# boost-demux_v1.net
KiCad netlist of a schematic drawn in EAGLE
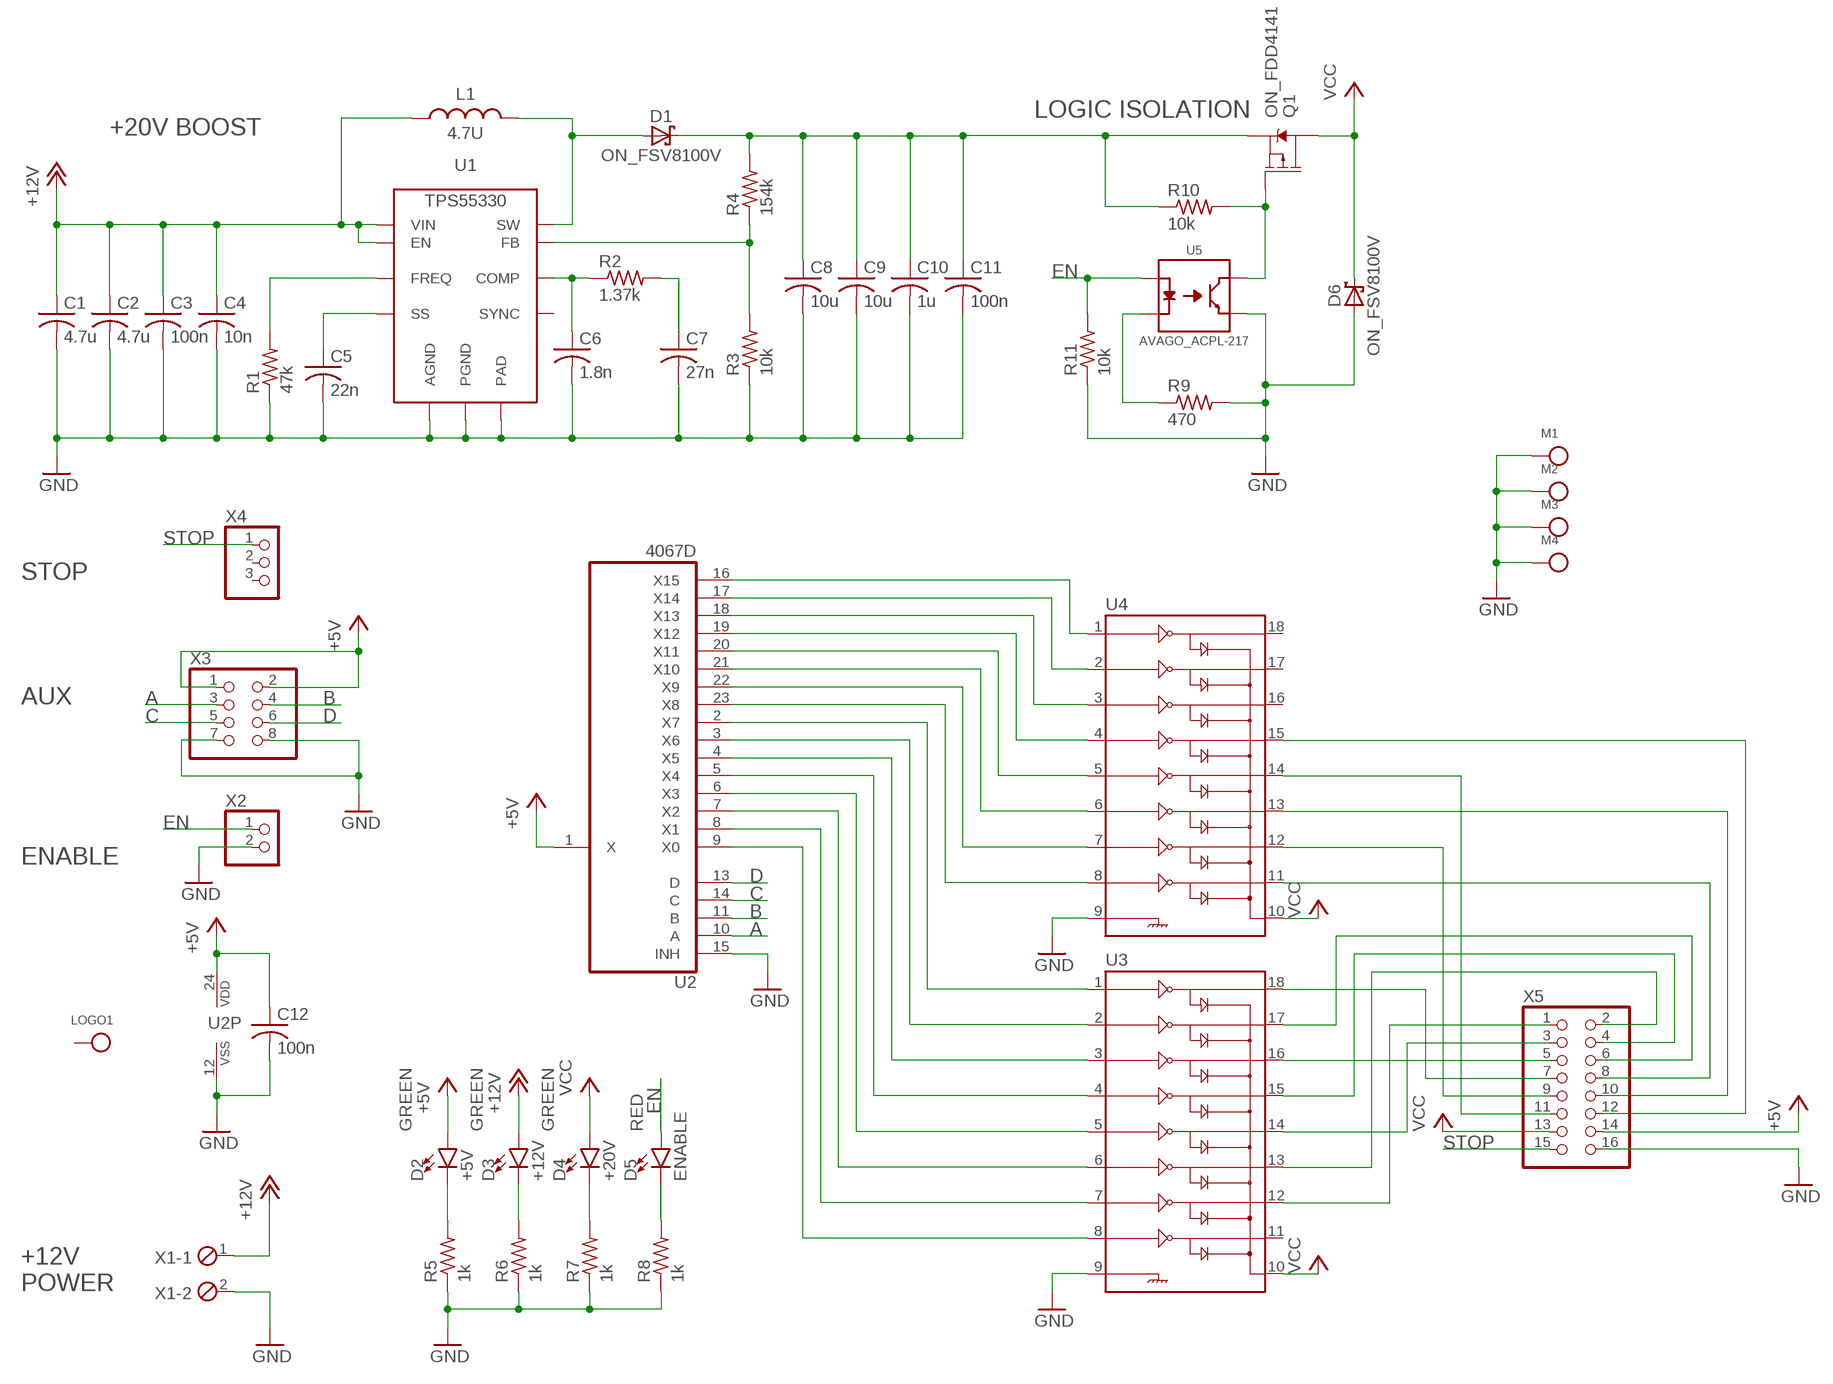
[diagram p0: schematic, sheet 1]

(export (version "E")
  (design (tool "Eeschema 10.0.6"))
  (components
    (comp (ref "C1")
      (value "4.7u")
      (footprint "eagle-import:C1206")
      (libsource (lib "eagle-import") (part "C-USC1206"))
    )
    (comp (ref "C2")
      (value "4.7u")
      (footprint "eagle-import:C1206")
      (libsource (lib "eagle-import") (part "C-USC1206"))
    )
    (comp (ref "C3")
      (value "100n")
      (footprint "eagle-import:C1206")
      (libsource (lib "eagle-import") (part "C-USC1206"))
    )
    (comp (ref "C4")
      (value "10n")
      (footprint "eagle-import:C1206")
      (libsource (lib "eagle-import") (part "C-USC1206"))
    )
    (comp (ref "C5")
      (value "22n")
      (footprint "eagle-import:C1206")
      (libsource (lib "eagle-import") (part "C-USC1206"))
    )
    (comp (ref "C6")
      (value "1.8n")
      (footprint "eagle-import:C0805")
      (libsource (lib "eagle-import") (part "C-USC0805"))
    )
    (comp (ref "C7")
      (value "27n")
      (footprint "eagle-import:C0805")
      (libsource (lib "eagle-import") (part "C-USC0805"))
    )
    (comp (ref "C8")
      (value "10u")
      (footprint "eagle-import:C1206")
      (libsource (lib "eagle-import") (part "C-USC1206"))
    )
    (comp (ref "C9")
      (value "10u")
      (footprint "eagle-import:C1206")
      (libsource (lib "eagle-import") (part "C-USC1206"))
    )
    (comp (ref "C10")
      (value "1u")
      (footprint "eagle-import:C1206")
      (libsource (lib "eagle-import") (part "C-USC1206"))
    )
    (comp (ref "C11")
      (value "100n")
      (footprint "eagle-import:C1206")
      (libsource (lib "eagle-import") (part "C-USC1206"))
    )
    (comp (ref "C12")
      (value "100n")
      (footprint "eagle-import:C1206")
      (libsource (lib "eagle-import") (part "C-USC1206"))
    )
    (comp (ref "D1")
      (value "ON_FSV8100V")
      (footprint "eagle-import:TO-277-3")
      (libsource (lib "eagle-import") (part "ON_FSV8100V"))
    )
    (comp (ref "D2")
      (value "+5V")
      (footprint "eagle-import:LED_5MM")
      (libsource (lib "eagle-import") (part "LED5MM"))
    )
    (comp (ref "D3")
      (value "+12V")
      (footprint "eagle-import:LED_5MM")
      (libsource (lib "eagle-import") (part "LED5MM"))
    )
    (comp (ref "D4")
      (value "+20V")
      (footprint "eagle-import:LED_5MM")
      (libsource (lib "eagle-import") (part "LED5MM"))
    )
    (comp (ref "D5")
      (value "ENABLE")
      (footprint "eagle-import:LED_5MM")
      (libsource (lib "eagle-import") (part "LED5MM"))
    )
    (comp (ref "D6")
      (value "ON_FSV8100V")
      (footprint "eagle-import:TO-277-3")
      (libsource (lib "eagle-import") (part "ON_FSV8100V"))
    )
    (comp (ref "L1")
      (value "4.7U")
      (footprint "eagle-import:4440")
      (libsource (lib "eagle-import") (part "MURATA_FDVE1040"))
    )
    (comp (ref "LOGO1")
      (value "MADOG")
      (footprint "eagle-import:MADOG")
      (libsource (lib "eagle-import") (part "MADOG"))
    )
    (comp (ref "M1")
      (value "6-32_MOUNT")
      (footprint "eagle-import:6-32_MOUNT")
      (libsource (lib "eagle-import") (part "6-32_MOUNT"))
    )
    (comp (ref "M2")
      (value "6-32_MOUNT")
      (footprint "eagle-import:6-32_MOUNT")
      (libsource (lib "eagle-import") (part "6-32_MOUNT"))
    )
    (comp (ref "M3")
      (value "6-32_MOUNT")
      (footprint "eagle-import:6-32_MOUNT")
      (libsource (lib "eagle-import") (part "6-32_MOUNT"))
    )
    (comp (ref "M4")
      (value "6-32_MOUNT")
      (footprint "eagle-import:6-32_MOUNT")
      (libsource (lib "eagle-import") (part "6-32_MOUNT"))
    )
    (comp (ref "Q1")
      (value "ON_FDD4141")
      (footprint "eagle-import:TO-252-3")
      (libsource (lib "eagle-import") (part "ON_FDD4141"))
    )
    (comp (ref "R1")
      (value "47k")
      (footprint "eagle-import:R1206")
      (libsource (lib "eagle-import") (part "R-US_R1206"))
    )
    (comp (ref "R2")
      (value "1.37k")
      (footprint "eagle-import:R0805")
      (libsource (lib "eagle-import") (part "R-US_R0805"))
    )
    (comp (ref "R3")
      (value "10k")
      (footprint "eagle-import:R0805")
      (libsource (lib "eagle-import") (part "R-US_R0805"))
    )
    (comp (ref "R4")
      (value "154k")
      (footprint "eagle-import:R0805")
      (libsource (lib "eagle-import") (part "R-US_R0805"))
    )
    (comp (ref "R5")
      (value "1k")
      (footprint "eagle-import:R1206")
      (libsource (lib "eagle-import") (part "resistor_348_R-US_R1206"))
    )
    (comp (ref "R6")
      (value "1k")
      (footprint "eagle-import:R1206")
      (libsource (lib "eagle-import") (part "resistor_348_R-US_R1206"))
    )
    (comp (ref "R7")
      (value "1k")
      (footprint "eagle-import:R1206")
      (libsource (lib "eagle-import") (part "resistor_348_R-US_R1206"))
    )
    (comp (ref "R8")
      (value "1k")
      (footprint "eagle-import:R1206")
      (libsource (lib "eagle-import") (part "resistor_348_R-US_R1206"))
    )
    (comp (ref "R9")
      (value "470")
      (footprint "eagle-import:R1206")
      (libsource (lib "eagle-import") (part "resistor_348_R-US_R1206"))
    )
    (comp (ref "R10")
      (value "10k")
      (footprint "eagle-import:R0805")
      (libsource (lib "eagle-import") (part "R-US_R0805"))
    )
    (comp (ref "R11")
      (value "10k")
      (footprint "eagle-import:R0805")
      (libsource (lib "eagle-import") (part "R-US_R0805"))
    )
    (comp (ref "U1")
      (value "TI_TPS55330")
      (footprint "eagle-import:S-PWQFN-N16")
      (libsource (lib "eagle-import") (part "TI_TPS55330"))
    )
    (comp (ref "U2")
      (value "4067D")
      (footprint "eagle-import:SO24W")
      (libsource (lib "eagle-import") (part "4067D"))
    )
    (comp (ref "U3")
      (value "ULN2803SOICW")
      (footprint "eagle-import:SO18L")
      (libsource (lib "eagle-import") (part "ULN2803SOICW"))
    )
    (comp (ref "U4")
      (value "ULN2803SOICW")
      (footprint "eagle-import:SO18L")
      (libsource (lib "eagle-import") (part "ULN2803SOICW"))
    )
    (comp (ref "U5")
      (value "AVAGO_ACPL-217")
      (footprint "eagle-import:SOIC-4")
      (libsource (lib "eagle-import") (part "AVAGO_ACPL-217"))
    )
    (comp (ref "X1")
      (value "MPT2")
      (footprint "eagle-import:2POL254")
      (libsource (lib "eagle-import") (part "MPT2"))
    )
    (comp (ref "X2")
      (value "PINHD-1X2/90")
      (footprint "eagle-import:1X02_90")
      (libsource (lib "eagle-import") (part "PINHD-1X2/90"))
    )
    (comp (ref "X3")
      (value "PINHD-2X4/90")
      (footprint "eagle-import:2X04_90")
      (libsource (lib "eagle-import") (part "PINHD-2X4/90"))
    )
    (comp (ref "X4")
      (value "PINHD-1X3/90")
      (footprint "eagle-import:1X03_90")
      (libsource (lib "eagle-import") (part "PINHD-1X3/90"))
    )
    (comp (ref "X5")
      (value "PINHD-2X8")
      (footprint "eagle-import:2X08")
      (libsource (lib "eagle-import") (part "PINHD-2X8"))
    )
  )
  (nets
    (net (code "1") (name "+5V") (class "Default")
      (node (ref "C12") (pin "1") (pinfunction "1_1") (pintype "passive"))
      (node (ref "D2") (pin "A") (pinfunction "A_A") (pintype "passive"))
      (node (ref "U2") (pin "1") (pinfunction "X_1") (pintype "output"))
      (node (ref "U2") (pin "24") (pinfunction "VDD_24") (pintype "power_in"))
      (node (ref "X3") (pin "1") (pinfunction "1_1") (pintype "passive"))
      (node (ref "X3") (pin "2") (pinfunction "2_2") (pintype "passive"))
      (node (ref "X5") (pin "14") (pinfunction "14_14") (pintype "passive"))
    )
    (net (code "2") (name "+12V") (class "Default")
      (node (ref "C1") (pin "1") (pinfunction "1_1") (pintype "passive"))
      (node (ref "C2") (pin "1") (pinfunction "1_1") (pintype "passive"))
      (node (ref "C3") (pin "1") (pinfunction "1_1") (pintype "passive"))
      (node (ref "C4") (pin "1") (pinfunction "1_1") (pintype "passive"))
      (node (ref "D3") (pin "A") (pinfunction "A_A") (pintype "passive"))
      (node (ref "L1") (pin "1") (pinfunction "1_1") (pintype "passive"))
      (node (ref "U1") (pin "2") (pinfunction "VIN_2") (pintype "passive"))
      (node (ref "U1") (pin "3") (pinfunction "EN_3") (pintype "passive"))
      (node (ref "X1") (pin "1") (pinfunction "1_1") (pintype "passive"))
    )
    (net (code "3") (name "/A") (class "Default")
      (node (ref "U2") (pin "10") (pinfunction "A_10") (pintype "input"))
      (node (ref "X3") (pin "3") (pinfunction "3_3") (pintype "passive"))
    )
    (net (code "4") (name "/B") (class "Default")
      (node (ref "U2") (pin "11") (pinfunction "B_11") (pintype "input"))
      (node (ref "X3") (pin "4") (pinfunction "4_4") (pintype "passive"))
    )
    (net (code "5") (name "/C") (class "Default")
      (node (ref "U2") (pin "14") (pinfunction "C_14") (pintype "input"))
      (node (ref "X3") (pin "5") (pinfunction "5_5") (pintype "passive"))
    )
    (net (code "6") (name "/D") (class "Default")
      (node (ref "U2") (pin "13") (pinfunction "D_13") (pintype "input"))
      (node (ref "X3") (pin "6") (pinfunction "6_6") (pintype "passive"))
    )
    (net (code "7") (name "/EN") (class "Default")
      (node (ref "D5") (pin "A") (pinfunction "A_A") (pintype "passive"))
      (node (ref "R11") (pin "2") (pinfunction "2_2") (pintype "passive"))
      (node (ref "U5") (pin "P$1") (pinfunction "P$1_P$1") (pintype "bidirectional"))
      (node (ref "X2") (pin "1") (pinfunction "1_1") (pintype "passive"))
    )
    (net (code "8") (name "/STOP") (class "Default")
      (node (ref "X4") (pin "1") (pinfunction "1_1") (pintype "passive"))
      (node (ref "X5") (pin "15") (pinfunction "15_15") (pintype "passive"))
    )
    (net (code "9") (name "GND") (class "Default")
      (node (ref "C1") (pin "2") (pinfunction "2_2") (pintype "passive"))
      (node (ref "C10") (pin "2") (pinfunction "2_2") (pintype "passive"))
      (node (ref "C11") (pin "2") (pinfunction "2_2") (pintype "passive"))
      (node (ref "C12") (pin "2") (pinfunction "2_2") (pintype "passive"))
      (node (ref "C2") (pin "2") (pinfunction "2_2") (pintype "passive"))
      (node (ref "C3") (pin "2") (pinfunction "2_2") (pintype "passive"))
      (node (ref "C4") (pin "2") (pinfunction "2_2") (pintype "passive"))
      (node (ref "C5") (pin "2") (pinfunction "2_2") (pintype "passive"))
      (node (ref "C6") (pin "2") (pinfunction "2_2") (pintype "passive"))
      (node (ref "C7") (pin "2") (pinfunction "2_2") (pintype "passive"))
      (node (ref "C8") (pin "2") (pinfunction "2_2") (pintype "passive"))
      (node (ref "C9") (pin "2") (pinfunction "2_2") (pintype "passive"))
      (node (ref "D6") (pin "P$1") (pinfunction "A_P$1") (pintype "passive"))
      (node (ref "D6") (pin "P$2") (pinfunction "A_P$2") (pintype "passive"))
      (node (ref "M1") (pin "P$1") (pinfunction "P$1_P$1") (pintype "bidirectional"))
      (node (ref "M1") (pin "P$2") (pinfunction "P$1_P$2") (pintype "bidirectional"))
      (node (ref "M1") (pin "P$3") (pinfunction "P$1_P$3") (pintype "bidirectional"))
      (node (ref "M1") (pin "P$4") (pinfunction "P$1_P$4") (pintype "bidirectional"))
      (node (ref "M1") (pin "P$5") (pinfunction "P$1_P$5") (pintype "bidirectional"))
      (node (ref "M1") (pin "P$6") (pinfunction "P$1_P$6") (pintype "bidirectional"))
      (node (ref "M1") (pin "P$7") (pinfunction "P$1_P$7") (pintype "bidirectional"))
      (node (ref "M1") (pin "P$8") (pinfunction "P$1_P$8") (pintype "bidirectional"))
      (node (ref "M1") (pin "P$9") (pinfunction "P$1_P$9") (pintype "bidirectional"))
      (node (ref "M2") (pin "P$1") (pinfunction "P$1_P$1") (pintype "bidirectional"))
      (node (ref "M2") (pin "P$2") (pinfunction "P$1_P$2") (pintype "bidirectional"))
      (node (ref "M2") (pin "P$3") (pinfunction "P$1_P$3") (pintype "bidirectional"))
      (node (ref "M2") (pin "P$4") (pinfunction "P$1_P$4") (pintype "bidirectional"))
      (node (ref "M2") (pin "P$5") (pinfunction "P$1_P$5") (pintype "bidirectional"))
      (node (ref "M2") (pin "P$6") (pinfunction "P$1_P$6") (pintype "bidirectional"))
      (node (ref "M2") (pin "P$7") (pinfunction "P$1_P$7") (pintype "bidirectional"))
      (node (ref "M2") (pin "P$8") (pinfunction "P$1_P$8") (pintype "bidirectional"))
      (node (ref "M2") (pin "P$9") (pinfunction "P$1_P$9") (pintype "bidirectional"))
      (node (ref "M3") (pin "P$1") (pinfunction "P$1_P$1") (pintype "bidirectional"))
      (node (ref "M3") (pin "P$2") (pinfunction "P$1_P$2") (pintype "bidirectional"))
      (node (ref "M3") (pin "P$3") (pinfunction "P$1_P$3") (pintype "bidirectional"))
      (node (ref "M3") (pin "P$4") (pinfunction "P$1_P$4") (pintype "bidirectional"))
      (node (ref "M3") (pin "P$5") (pinfunction "P$1_P$5") (pintype "bidirectional"))
      (node (ref "M3") (pin "P$6") (pinfunction "P$1_P$6") (pintype "bidirectional"))
      (node (ref "M3") (pin "P$7") (pinfunction "P$1_P$7") (pintype "bidirectional"))
      (node (ref "M3") (pin "P$8") (pinfunction "P$1_P$8") (pintype "bidirectional"))
      (node (ref "M3") (pin "P$9") (pinfunction "P$1_P$9") (pintype "bidirectional"))
      (node (ref "M4") (pin "P$1") (pinfunction "P$1_P$1") (pintype "bidirectional"))
      (node (ref "M4") (pin "P$2") (pinfunction "P$1_P$2") (pintype "bidirectional"))
      (node (ref "M4") (pin "P$3") (pinfunction "P$1_P$3") (pintype "bidirectional"))
      (node (ref "M4") (pin "P$4") (pinfunction "P$1_P$4") (pintype "bidirectional"))
      (node (ref "M4") (pin "P$5") (pinfunction "P$1_P$5") (pintype "bidirectional"))
      (node (ref "M4") (pin "P$6") (pinfunction "P$1_P$6") (pintype "bidirectional"))
      (node (ref "M4") (pin "P$7") (pinfunction "P$1_P$7") (pintype "bidirectional"))
      (node (ref "M4") (pin "P$8") (pinfunction "P$1_P$8") (pintype "bidirectional"))
      (node (ref "M4") (pin "P$9") (pinfunction "P$1_P$9") (pintype "bidirectional"))
      (node (ref "R1") (pin "1") (pinfunction "1_1") (pintype "passive"))
      (node (ref "R11") (pin "1") (pinfunction "1_1") (pintype "passive"))
      (node (ref "R3") (pin "1") (pinfunction "1_1") (pintype "passive"))
      (node (ref "R5") (pin "1") (pinfunction "1_1") (pintype "passive"))
      (node (ref "R6") (pin "1") (pinfunction "1_1") (pintype "passive"))
      (node (ref "R7") (pin "1") (pinfunction "1_1") (pintype "passive"))
      (node (ref "R8") (pin "1") (pinfunction "1_1") (pintype "passive"))
      (node (ref "R9") (pin "2") (pinfunction "2_2") (pintype "passive"))
      (node (ref "U1") (pin "11") (pinfunction "PGND_11") (pintype "passive"))
      (node (ref "U1") (pin "12") (pinfunction "PGND_12") (pintype "passive"))
      (node (ref "U1") (pin "13") (pinfunction "PGND_13") (pintype "passive"))
      (node (ref "U1") (pin "6") (pinfunction "AGND_6") (pintype "passive"))
      (node (ref "U1") (pin "PAD") (pinfunction "PAD_PAD") (pintype "bidirectional"))
      (node (ref "U2") (pin "12") (pinfunction "VSS_12") (pintype "power_in"))
      (node (ref "U2") (pin "15") (pinfunction "INH_15") (pintype "input"))
      (node (ref "U3") (pin "9") (pinfunction "9_9") (pintype "bidirectional"))
      (node (ref "U4") (pin "9") (pinfunction "9_9") (pintype "bidirectional"))
      (node (ref "U5") (pin "P$3") (pinfunction "P$3_P$3") (pintype "bidirectional"))
      (node (ref "X1") (pin "2") (pinfunction "1_2") (pintype "passive"))
      (node (ref "X2") (pin "2") (pinfunction "2_2") (pintype "passive"))
      (node (ref "X3") (pin "7") (pinfunction "7_7") (pintype "passive"))
      (node (ref "X3") (pin "8") (pinfunction "8_8") (pintype "passive"))
      (node (ref "X5") (pin "16") (pinfunction "16_16") (pintype "passive"))
    )
    (net (code "10") (name "Net-(C7-Pad1)") (class "Default")
      (node (ref "C7") (pin "1") (pinfunction "1_1") (pintype "passive"))
      (node (ref "R2") (pin "2") (pinfunction "2_2") (pintype "passive"))
    )
    (net (code "11") (name "Net-(D1-A-PadP$1)") (class "Default")
      (node (ref "D1") (pin "P$1") (pinfunction "A_P$1") (pintype "passive"))
      (node (ref "D1") (pin "P$2") (pinfunction "A_P$2") (pintype "passive"))
      (node (ref "L1") (pin "2") (pinfunction "2_2") (pintype "passive"))
      (node (ref "U1") (pin "1") (pinfunction "SW_1") (pintype "passive"))
      (node (ref "U1") (pin "15") (pinfunction "SW_15") (pintype "passive"))
      (node (ref "U1") (pin "16") (pinfunction "SW_16") (pintype "passive"))
    )
    (net (code "12") (name "Net-(D1-C)") (class "Default")
      (node (ref "C10") (pin "1") (pinfunction "1_1") (pintype "passive"))
      (node (ref "C11") (pin "1") (pinfunction "1_1") (pintype "passive"))
      (node (ref "C8") (pin "1") (pinfunction "1_1") (pintype "passive"))
      (node (ref "C9") (pin "1") (pinfunction "1_1") (pintype "passive"))
      (node (ref "D1") (pin "P$3") (pinfunction "C_P$3") (pintype "passive"))
      (node (ref "Q1") (pin "P$3") (pinfunction "S_P$3") (pintype "bidirectional"))
      (node (ref "R10") (pin "1") (pinfunction "1_1") (pintype "passive"))
      (node (ref "R4") (pin "2") (pinfunction "2_2") (pintype "passive"))
    )
    (net (code "13") (name "Net-(D2-C)") (class "Default")
      (node (ref "D2") (pin "K") (pinfunction "C_K") (pintype "passive"))
      (node (ref "R5") (pin "2") (pinfunction "2_2") (pintype "passive"))
    )
    (net (code "14") (name "Net-(D3-C)") (class "Default")
      (node (ref "D3") (pin "K") (pinfunction "C_K") (pintype "passive"))
      (node (ref "R6") (pin "2") (pinfunction "2_2") (pintype "passive"))
    )
    (net (code "15") (name "Net-(D4-C)") (class "Default")
      (node (ref "D4") (pin "K") (pinfunction "C_K") (pintype "passive"))
      (node (ref "R7") (pin "2") (pinfunction "2_2") (pintype "passive"))
    )
    (net (code "16") (name "Net-(D5-C)") (class "Default")
      (node (ref "D5") (pin "K") (pinfunction "C_K") (pintype "passive"))
      (node (ref "R8") (pin "2") (pinfunction "2_2") (pintype "passive"))
    )
    (net (code "17") (name "Net-(Q1-G)") (class "Default")
      (node (ref "Q1") (pin "P$1") (pinfunction "G_P$1") (pintype "bidirectional"))
      (node (ref "R10") (pin "2") (pinfunction "2_2") (pintype "passive"))
      (node (ref "U5") (pin "P$4") (pinfunction "P$4_P$4") (pintype "bidirectional"))
    )
    (net (code "18") (name "Net-(R9-Pad1)") (class "Default")
      (node (ref "R9") (pin "1") (pinfunction "1_1") (pintype "passive"))
      (node (ref "U5") (pin "P$2") (pinfunction "P$2_P$2") (pintype "bidirectional"))
    )
    (net (code "19") (name "Net-(U1-COMP)") (class "Default")
      (node (ref "C6") (pin "1") (pinfunction "1_1") (pintype "passive"))
      (node (ref "R2") (pin "1") (pinfunction "1_1") (pintype "passive"))
      (node (ref "U1") (pin "7") (pinfunction "COMP_7") (pintype "passive"))
    )
    (net (code "20") (name "Net-(U1-FB)") (class "Default")
      (node (ref "R3") (pin "2") (pinfunction "2_2") (pintype "passive"))
      (node (ref "R4") (pin "1") (pinfunction "1_1") (pintype "passive"))
      (node (ref "U1") (pin "8") (pinfunction "FB_8") (pintype "passive"))
    )
    (net (code "21") (name "Net-(U1-FREQ)") (class "Default")
      (node (ref "R1") (pin "2") (pinfunction "2_2") (pintype "passive"))
      (node (ref "U1") (pin "9") (pinfunction "FREQ_9") (pintype "passive"))
    )
    (net (code "22") (name "Net-(U1-SS)") (class "Default")
      (node (ref "C5") (pin "1") (pinfunction "1_1") (pintype "passive"))
      (node (ref "U1") (pin "4") (pinfunction "SS_4") (pintype "passive"))
    )
    (net (code "23") (name "Net-(U2A-X0)") (class "Default")
      (node (ref "U2") (pin "9") (pinfunction "X0_9") (pintype "input"))
      (node (ref "U3") (pin "8") (pinfunction "8_8") (pintype "bidirectional"))
    )
    (net (code "24") (name "Net-(U2A-X1)") (class "Default")
      (node (ref "U2") (pin "8") (pinfunction "X1_8") (pintype "input"))
      (node (ref "U3") (pin "7") (pinfunction "7_7") (pintype "bidirectional"))
    )
    (net (code "25") (name "Net-(U2A-X2)") (class "Default")
      (node (ref "U2") (pin "7") (pinfunction "X2_7") (pintype "input"))
      (node (ref "U3") (pin "6") (pinfunction "6_6") (pintype "bidirectional"))
    )
    (net (code "26") (name "Net-(U2A-X3)") (class "Default")
      (node (ref "U2") (pin "6") (pinfunction "X3_6") (pintype "input"))
      (node (ref "U3") (pin "5") (pinfunction "5_5") (pintype "bidirectional"))
    )
    (net (code "27") (name "Net-(U2A-X4)") (class "Default")
      (node (ref "U2") (pin "5") (pinfunction "X4_5") (pintype "input"))
      (node (ref "U3") (pin "4") (pinfunction "4_4") (pintype "bidirectional"))
    )
    (net (code "28") (name "Net-(U2A-X5)") (class "Default")
      (node (ref "U2") (pin "4") (pinfunction "X5_4") (pintype "input"))
      (node (ref "U3") (pin "3") (pinfunction "3_3") (pintype "bidirectional"))
    )
    (net (code "29") (name "Net-(U2A-X6)") (class "Default")
      (node (ref "U2") (pin "3") (pinfunction "X6_3") (pintype "input"))
      (node (ref "U3") (pin "2") (pinfunction "2_2") (pintype "bidirectional"))
    )
    (net (code "30") (name "Net-(U2A-X7)") (class "Default")
      (node (ref "U2") (pin "2") (pinfunction "X7_2") (pintype "input"))
      (node (ref "U3") (pin "1") (pinfunction "1_1") (pintype "bidirectional"))
    )
    (net (code "31") (name "Net-(U2A-X8)") (class "Default")
      (node (ref "U2") (pin "23") (pinfunction "X8_23") (pintype "input"))
      (node (ref "U4") (pin "8") (pinfunction "8_8") (pintype "bidirectional"))
    )
    (net (code "32") (name "Net-(U2A-X9)") (class "Default")
      (node (ref "U2") (pin "22") (pinfunction "X9_22") (pintype "input"))
      (node (ref "U4") (pin "7") (pinfunction "7_7") (pintype "bidirectional"))
    )
    (net (code "33") (name "Net-(U2A-X10)") (class "Default")
      (node (ref "U2") (pin "21") (pinfunction "X10_21") (pintype "input"))
      (node (ref "U4") (pin "6") (pinfunction "6_6") (pintype "bidirectional"))
    )
    (net (code "34") (name "Net-(U2A-X11)") (class "Default")
      (node (ref "U2") (pin "20") (pinfunction "X11_20") (pintype "input"))
      (node (ref "U4") (pin "5") (pinfunction "5_5") (pintype "bidirectional"))
    )
    (net (code "35") (name "Net-(U2A-X12)") (class "Default")
      (node (ref "U2") (pin "19") (pinfunction "X12_19") (pintype "input"))
      (node (ref "U4") (pin "4") (pinfunction "4_4") (pintype "bidirectional"))
    )
    (net (code "36") (name "Net-(U2A-X13)") (class "Default")
      (node (ref "U2") (pin "18") (pinfunction "X13_18") (pintype "input"))
      (node (ref "U4") (pin "3") (pinfunction "3_3") (pintype "bidirectional"))
    )
    (net (code "37") (name "Net-(U2A-X14)") (class "Default")
      (node (ref "U2") (pin "17") (pinfunction "X14_17") (pintype "input"))
      (node (ref "U4") (pin "2") (pinfunction "2_2") (pintype "bidirectional"))
    )
    (net (code "38") (name "Net-(U2A-X15)") (class "Default")
      (node (ref "U2") (pin "16") (pinfunction "X15_16") (pintype "input"))
      (node (ref "U4") (pin "1") (pinfunction "1_1") (pintype "bidirectional"))
    )
    (net (code "39") (name "Net-(U3-Pad12)") (class "Default")
      (node (ref "U3") (pin "12") (pinfunction "12_12") (pintype "bidirectional"))
      (node (ref "X5") (pin "1") (pinfunction "1_1") (pintype "passive"))
    )
    (net (code "40") (name "Net-(U3-Pad13)") (class "Default")
      (node (ref "U3") (pin "13") (pinfunction "13_13") (pintype "bidirectional"))
      (node (ref "X5") (pin "2") (pinfunction "2_2") (pintype "passive"))
    )
    (net (code "41") (name "Net-(U3-Pad14)") (class "Default")
      (node (ref "U3") (pin "14") (pinfunction "14_14") (pintype "bidirectional"))
      (node (ref "X5") (pin "3") (pinfunction "3_3") (pintype "passive"))
    )
    (net (code "42") (name "Net-(U3-Pad15)") (class "Default")
      (node (ref "U3") (pin "15") (pinfunction "15_15") (pintype "bidirectional"))
      (node (ref "X5") (pin "4") (pinfunction "4_4") (pintype "passive"))
    )
    (net (code "43") (name "Net-(U3-Pad16)") (class "Default")
      (node (ref "U3") (pin "16") (pinfunction "16_16") (pintype "bidirectional"))
      (node (ref "X5") (pin "5") (pinfunction "5_5") (pintype "passive"))
    )
    (net (code "44") (name "Net-(U3-Pad17)") (class "Default")
      (node (ref "U3") (pin "17") (pinfunction "17_17") (pintype "bidirectional"))
      (node (ref "X5") (pin "6") (pinfunction "6_6") (pintype "passive"))
    )
    (net (code "45") (name "Net-(U3-Pad18)") (class "Default")
      (node (ref "U3") (pin "18") (pinfunction "18_18") (pintype "bidirectional"))
      (node (ref "X5") (pin "7") (pinfunction "7_7") (pintype "passive"))
    )
    (net (code "46") (name "Net-(U4-Pad11)") (class "Default")
      (node (ref "U4") (pin "11") (pinfunction "11_11") (pintype "bidirectional"))
      (node (ref "X5") (pin "8") (pinfunction "8_8") (pintype "passive"))
    )
    (net (code "47") (name "Net-(U4-Pad12)") (class "Default")
      (node (ref "U4") (pin "12") (pinfunction "12_12") (pintype "bidirectional"))
      (node (ref "X5") (pin "9") (pinfunction "9_9") (pintype "passive"))
    )
    (net (code "48") (name "Net-(U4-Pad13)") (class "Default")
      (node (ref "U4") (pin "13") (pinfunction "13_13") (pintype "bidirectional"))
      (node (ref "X5") (pin "10") (pinfunction "10_10") (pintype "passive"))
    )
    (net (code "49") (name "Net-(U4-Pad14)") (class "Default")
      (node (ref "U4") (pin "14") (pinfunction "14_14") (pintype "bidirectional"))
      (node (ref "X5") (pin "11") (pinfunction "11_11") (pintype "passive"))
    )
    (net (code "50") (name "Net-(U4-Pad15)") (class "Default")
      (node (ref "U4") (pin "15") (pinfunction "15_15") (pintype "bidirectional"))
      (node (ref "X5") (pin "12") (pinfunction "12_12") (pintype "passive"))
    )
    (net (code "51") (name "VCC") (class "Default")
      (node (ref "D4") (pin "A") (pinfunction "A_A") (pintype "passive"))
      (node (ref "D6") (pin "P$3") (pinfunction "C_P$3") (pintype "passive"))
      (node (ref "Q1") (pin "P$4") (pinfunction "D_P$4") (pintype "bidirectional"))
      (node (ref "U3") (pin "10") (pinfunction "10_10") (pintype "bidirectional"))
      (node (ref "U4") (pin "10") (pinfunction "10_10") (pintype "bidirectional"))
      (node (ref "X5") (pin "13") (pinfunction "13_13") (pintype "passive"))
    )
    (net (code "52") (name "unconnected-(LOGO1-PadP$1)") (class "Default")
      (node (ref "LOGO1") (pin "P$1") (pinfunction "P$1_P$1") (pintype "bidirectional"))
    )
    (net (code "53") (name "unconnected-(U1-SYNC-Pad5)") (class "Default")
      (node (ref "U1") (pin "5") (pinfunction "SYNC_5") (pintype "passive"))
    )
    (net (code "54") (name "unconnected-(U3-Pad11)") (class "Default")
      (node (ref "U3") (pin "11") (pinfunction "11_11") (pintype "bidirectional"))
    )
    (net (code "55") (name "unconnected-(U4-Pad16)") (class "Default")
      (node (ref "U4") (pin "16") (pinfunction "16_16") (pintype "bidirectional"))
    )
    (net (code "56") (name "unconnected-(U4-Pad17)") (class "Default")
      (node (ref "U4") (pin "17") (pinfunction "17_17") (pintype "bidirectional"))
    )
    (net (code "57") (name "unconnected-(U4-Pad18)") (class "Default")
      (node (ref "U4") (pin "18") (pinfunction "18_18") (pintype "bidirectional"))
    )
    (net (code "58") (name "unconnected-(X4-Pad2)") (class "Default")
      (node (ref "X4") (pin "2") (pinfunction "2_2") (pintype "passive"))
    )
    (net (code "59") (name "unconnected-(X4-Pad3)") (class "Default")
      (node (ref "X4") (pin "3") (pinfunction "3_3") (pintype "passive"))
    )
  )
)
